# HyperRAM.net
KiCad netlist of a schematic drawn in Altium Designer
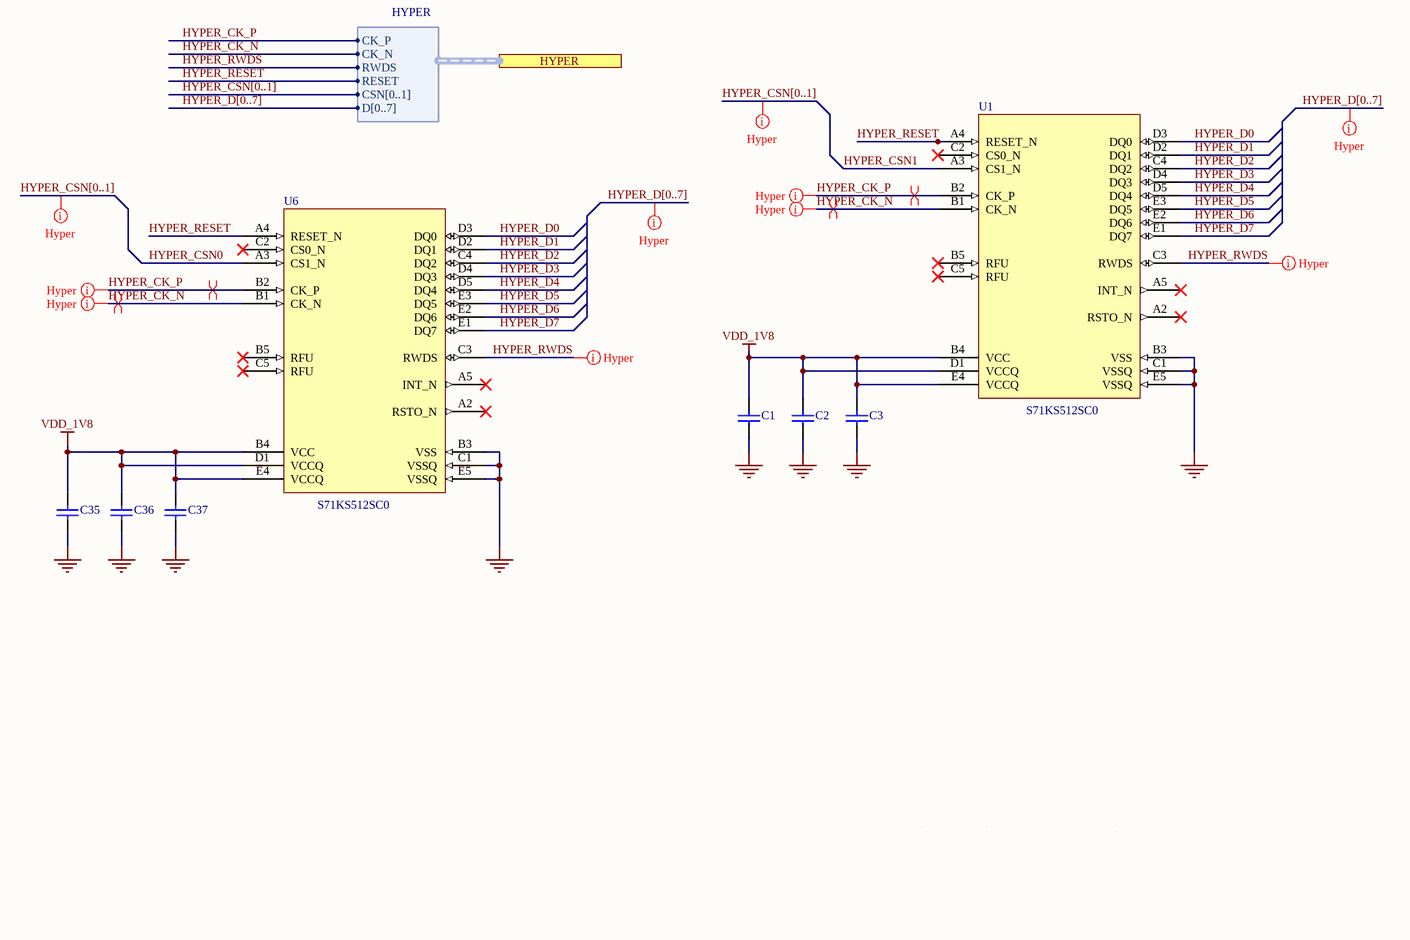
[diagram p0: HyperRAM.SchDoc]

(export (version "E")
  (design (tool "Eeschema 10.0.6"))
  (components
    (comp (ref "C1")
      (value "VJ0603Y104KNXAO")
      (footprint "CAPC1608X92X38LL15T08")
      (fields (field (name "MANUFACTURER") "Vitramon"))
      (libsource (lib "Altium Content Vault") (part "CAP"))
    )
    (comp (ref "C2")
      (value "VJ0603Y104KNXAO")
      (footprint "CAPC1608X92X38LL15T08")
      (fields (field (name "MANUFACTURER") "Vitramon"))
      (libsource (lib "Altium Content Vault") (part "CAP"))
    )
    (comp (ref "C3")
      (value "VJ0603Y104KNXAO")
      (footprint "CAPC1608X92X38LL15T08")
      (fields (field (name "MANUFACTURER") "Vitramon"))
      (libsource (lib "Altium Content Vault") (part "CAP"))
    )
    (comp (ref "C35")
      (value "VJ0603Y104KNXAO")
      (footprint "CAPC1608X92X38LL15T08")
      (fields (field (name "MANUFACTURER") "Vitramon"))
      (libsource (lib "Altium Content Vault") (part "CAP"))
    )
    (comp (ref "C36")
      (value "VJ0603Y104KNXAO")
      (footprint "CAPC1608X92X38LL15T08")
      (fields (field (name "MANUFACTURER") "Vitramon"))
      (libsource (lib "Altium Content Vault") (part "CAP"))
    )
    (comp (ref "C37")
      (value "VJ0603Y104KNXAO")
      (footprint "CAPC1608X92X38LL15T08")
      (fields (field (name "MANUFACTURER") "Vitramon"))
      (libsource (lib "Altium Content Vault") (part "CAP"))
    )
    (comp (ref "U1")
      (value "S71KS512SC0")
      (footprint "FBGA24_A-130")
      (libsource (lib "Hyperram") (part "S71KS512SC0"))
    )
    (comp (ref "U6")
      (value "S71KS512SC0")
      (footprint "FBGA24_A-130")
      (libsource (lib "Hyperram") (part "S71KS512SC0"))
    )
  )
  (nets
    (net (code "2") (name "/HYPER_CK_N") (class "Default")
      (node (ref "U1") (pin "B1") (pinfunction "CK_N_B1") (pintype "input"))
      (node (ref "U6") (pin "B1") (pinfunction "CK_N_B1") (pintype "input"))
    )
    (net (code "3") (name "/HYPER_CK_P") (class "Default")
      (node (ref "U1") (pin "B2") (pinfunction "CK_P_B2") (pintype "input"))
      (node (ref "U6") (pin "B2") (pinfunction "CK_P_B2") (pintype "input"))
    )
    (net (code "4") (name "/HYPER_CSN0") (class "Default")
      (node (ref "U6") (pin "A3") (pinfunction "CS1_N_A3") (pintype "input"))
    )
    (net (code "5") (name "/HYPER_CSN1") (class "Default")
      (node (ref "U1") (pin "A3") (pinfunction "CS1_N_A3") (pintype "input"))
    )
    (net (code "7") (name "/HYPER_D0") (class "Default")
      (node (ref "U1") (pin "D3") (pinfunction "DQ0_D3") (pintype "bidirectional"))
      (node (ref "U6") (pin "D3") (pinfunction "DQ0_D3") (pintype "bidirectional"))
    )
    (net (code "8") (name "/HYPER_D1") (class "Default")
      (node (ref "U1") (pin "D2") (pinfunction "DQ1_D2") (pintype "bidirectional"))
      (node (ref "U6") (pin "D2") (pinfunction "DQ1_D2") (pintype "bidirectional"))
    )
    (net (code "9") (name "/HYPER_D2") (class "Default")
      (node (ref "U1") (pin "C4") (pinfunction "DQ2_C4") (pintype "bidirectional"))
      (node (ref "U6") (pin "C4") (pinfunction "DQ2_C4") (pintype "bidirectional"))
    )
    (net (code "10") (name "/HYPER_D3") (class "Default")
      (node (ref "U1") (pin "D4") (pinfunction "DQ3_D4") (pintype "bidirectional"))
      (node (ref "U6") (pin "D4") (pinfunction "DQ3_D4") (pintype "bidirectional"))
    )
    (net (code "11") (name "/HYPER_D4") (class "Default")
      (node (ref "U1") (pin "D5") (pinfunction "DQ4_D5") (pintype "bidirectional"))
      (node (ref "U6") (pin "D5") (pinfunction "DQ4_D5") (pintype "bidirectional"))
    )
    (net (code "12") (name "/HYPER_D5") (class "Default")
      (node (ref "U1") (pin "E3") (pinfunction "DQ5_E3") (pintype "bidirectional"))
      (node (ref "U6") (pin "E3") (pinfunction "DQ5_E3") (pintype "bidirectional"))
    )
    (net (code "13") (name "/HYPER_D6") (class "Default")
      (node (ref "U1") (pin "E2") (pinfunction "DQ6_E2") (pintype "bidirectional"))
      (node (ref "U6") (pin "E2") (pinfunction "DQ6_E2") (pintype "bidirectional"))
    )
    (net (code "14") (name "/HYPER_D7") (class "Default")
      (node (ref "U1") (pin "E1") (pinfunction "DQ7_E1") (pintype "bidirectional"))
      (node (ref "U6") (pin "E1") (pinfunction "DQ7_E1") (pintype "bidirectional"))
    )
    (net (code "16") (name "/HYPER_RESET") (class "Default")
      (node (ref "U1") (pin "A4") (pinfunction "RESET_N_A4") (pintype "input"))
      (node (ref "U6") (pin "A4") (pinfunction "RESET_N_A4") (pintype "input"))
    )
    (net (code "17") (name "/HYPER_RWDS") (class "Default")
      (node (ref "U1") (pin "C3") (pinfunction "RWDS_C3") (pintype "bidirectional"))
      (node (ref "U6") (pin "C3") (pinfunction "RWDS_C3") (pintype "bidirectional"))
    )
    (net (code "19") (name "GND") (class "Default")
      (node (ref "C1") (pin "1") (pinfunction "1_1") (pintype "passive"))
      (node (ref "C2") (pin "1") (pinfunction "1_1") (pintype "passive"))
      (node (ref "C3") (pin "1") (pinfunction "1_1") (pintype "passive"))
      (node (ref "C35") (pin "1") (pinfunction "1_1") (pintype "passive"))
      (node (ref "C36") (pin "1") (pinfunction "1_1") (pintype "passive"))
      (node (ref "C37") (pin "1") (pinfunction "1_1") (pintype "passive"))
      (node (ref "U1") (pin "B3") (pinfunction "VSS_B3") (pintype "input"))
      (node (ref "U1") (pin "C1") (pinfunction "VSSQ_C1") (pintype "input"))
      (node (ref "U1") (pin "E5") (pinfunction "VSSQ_E5") (pintype "input"))
      (node (ref "U6") (pin "B3") (pinfunction "VSS_B3") (pintype "input"))
      (node (ref "U6") (pin "C1") (pinfunction "VSSQ_C1") (pintype "input"))
      (node (ref "U6") (pin "E5") (pinfunction "VSSQ_E5") (pintype "input"))
    )
    (net (code "20") (name "VDD_1V8") (class "Default")
      (node (ref "C1") (pin "2") (pinfunction "2_2") (pintype "passive"))
      (node (ref "C2") (pin "2") (pinfunction "2_2") (pintype "passive"))
      (node (ref "C3") (pin "2") (pinfunction "2_2") (pintype "passive"))
      (node (ref "C35") (pin "2") (pinfunction "2_2") (pintype "passive"))
      (node (ref "C36") (pin "2") (pinfunction "2_2") (pintype "passive"))
      (node (ref "C37") (pin "2") (pinfunction "2_2") (pintype "passive"))
      (node (ref "U1") (pin "B4") (pinfunction "VCC_B4") (pintype "power_in"))
      (node (ref "U1") (pin "D1") (pinfunction "VCCQ_D1") (pintype "power_in"))
      (node (ref "U1") (pin "E4") (pinfunction "VCCQ_E4") (pintype "power_in"))
      (node (ref "U6") (pin "B4") (pinfunction "VCC_B4") (pintype "power_in"))
      (node (ref "U6") (pin "D1") (pinfunction "VCCQ_D1") (pintype "power_in"))
      (node (ref "U6") (pin "E4") (pinfunction "VCCQ_E4") (pintype "power_in"))
    )
    (net (code "21") (name "unconnected-(U1-CS0_N-PadC2)") (class "Default")
      (node (ref "U1") (pin "C2") (pinfunction "CS0_N_C2") (pintype "input+no_connect"))
    )
    (net (code "22") (name "unconnected-(U1-INT_N-PadA5)") (class "Default")
      (node (ref "U1") (pin "A5") (pinfunction "INT_N_A5") (pintype "output+no_connect"))
    )
    (net (code "23") (name "unconnected-(U1-RFU-PadB5)") (class "Default")
      (node (ref "U1") (pin "B5") (pinfunction "RFU_B5") (pintype "input+no_connect"))
    )
    (net (code "24") (name "unconnected-(U1-RFU-PadC5)") (class "Default")
      (node (ref "U1") (pin "C5") (pinfunction "RFU_C5") (pintype "input+no_connect"))
    )
    (net (code "25") (name "unconnected-(U1-RSTO_N-PadA2)") (class "Default")
      (node (ref "U1") (pin "A2") (pinfunction "RSTO_N_A2") (pintype "output+no_connect"))
    )
    (net (code "26") (name "unconnected-(U6-CS0_N-PadC2)") (class "Default")
      (node (ref "U6") (pin "C2") (pinfunction "CS0_N_C2") (pintype "input+no_connect"))
    )
    (net (code "27") (name "unconnected-(U6-INT_N-PadA5)") (class "Default")
      (node (ref "U6") (pin "A5") (pinfunction "INT_N_A5") (pintype "output+no_connect"))
    )
    (net (code "28") (name "unconnected-(U6-RFU-PadB5)") (class "Default")
      (node (ref "U6") (pin "B5") (pinfunction "RFU_B5") (pintype "input+no_connect"))
    )
    (net (code "29") (name "unconnected-(U6-RFU-PadC5)") (class "Default")
      (node (ref "U6") (pin "C5") (pinfunction "RFU_C5") (pintype "input+no_connect"))
    )
    (net (code "30") (name "unconnected-(U6-RSTO_N-PadA2)") (class "Default")
      (node (ref "U6") (pin "A2") (pinfunction "RSTO_N_A2") (pintype "output+no_connect"))
    )
  )
)
